# MPU.net
KiCad netlist of a schematic drawn in Altium Designer
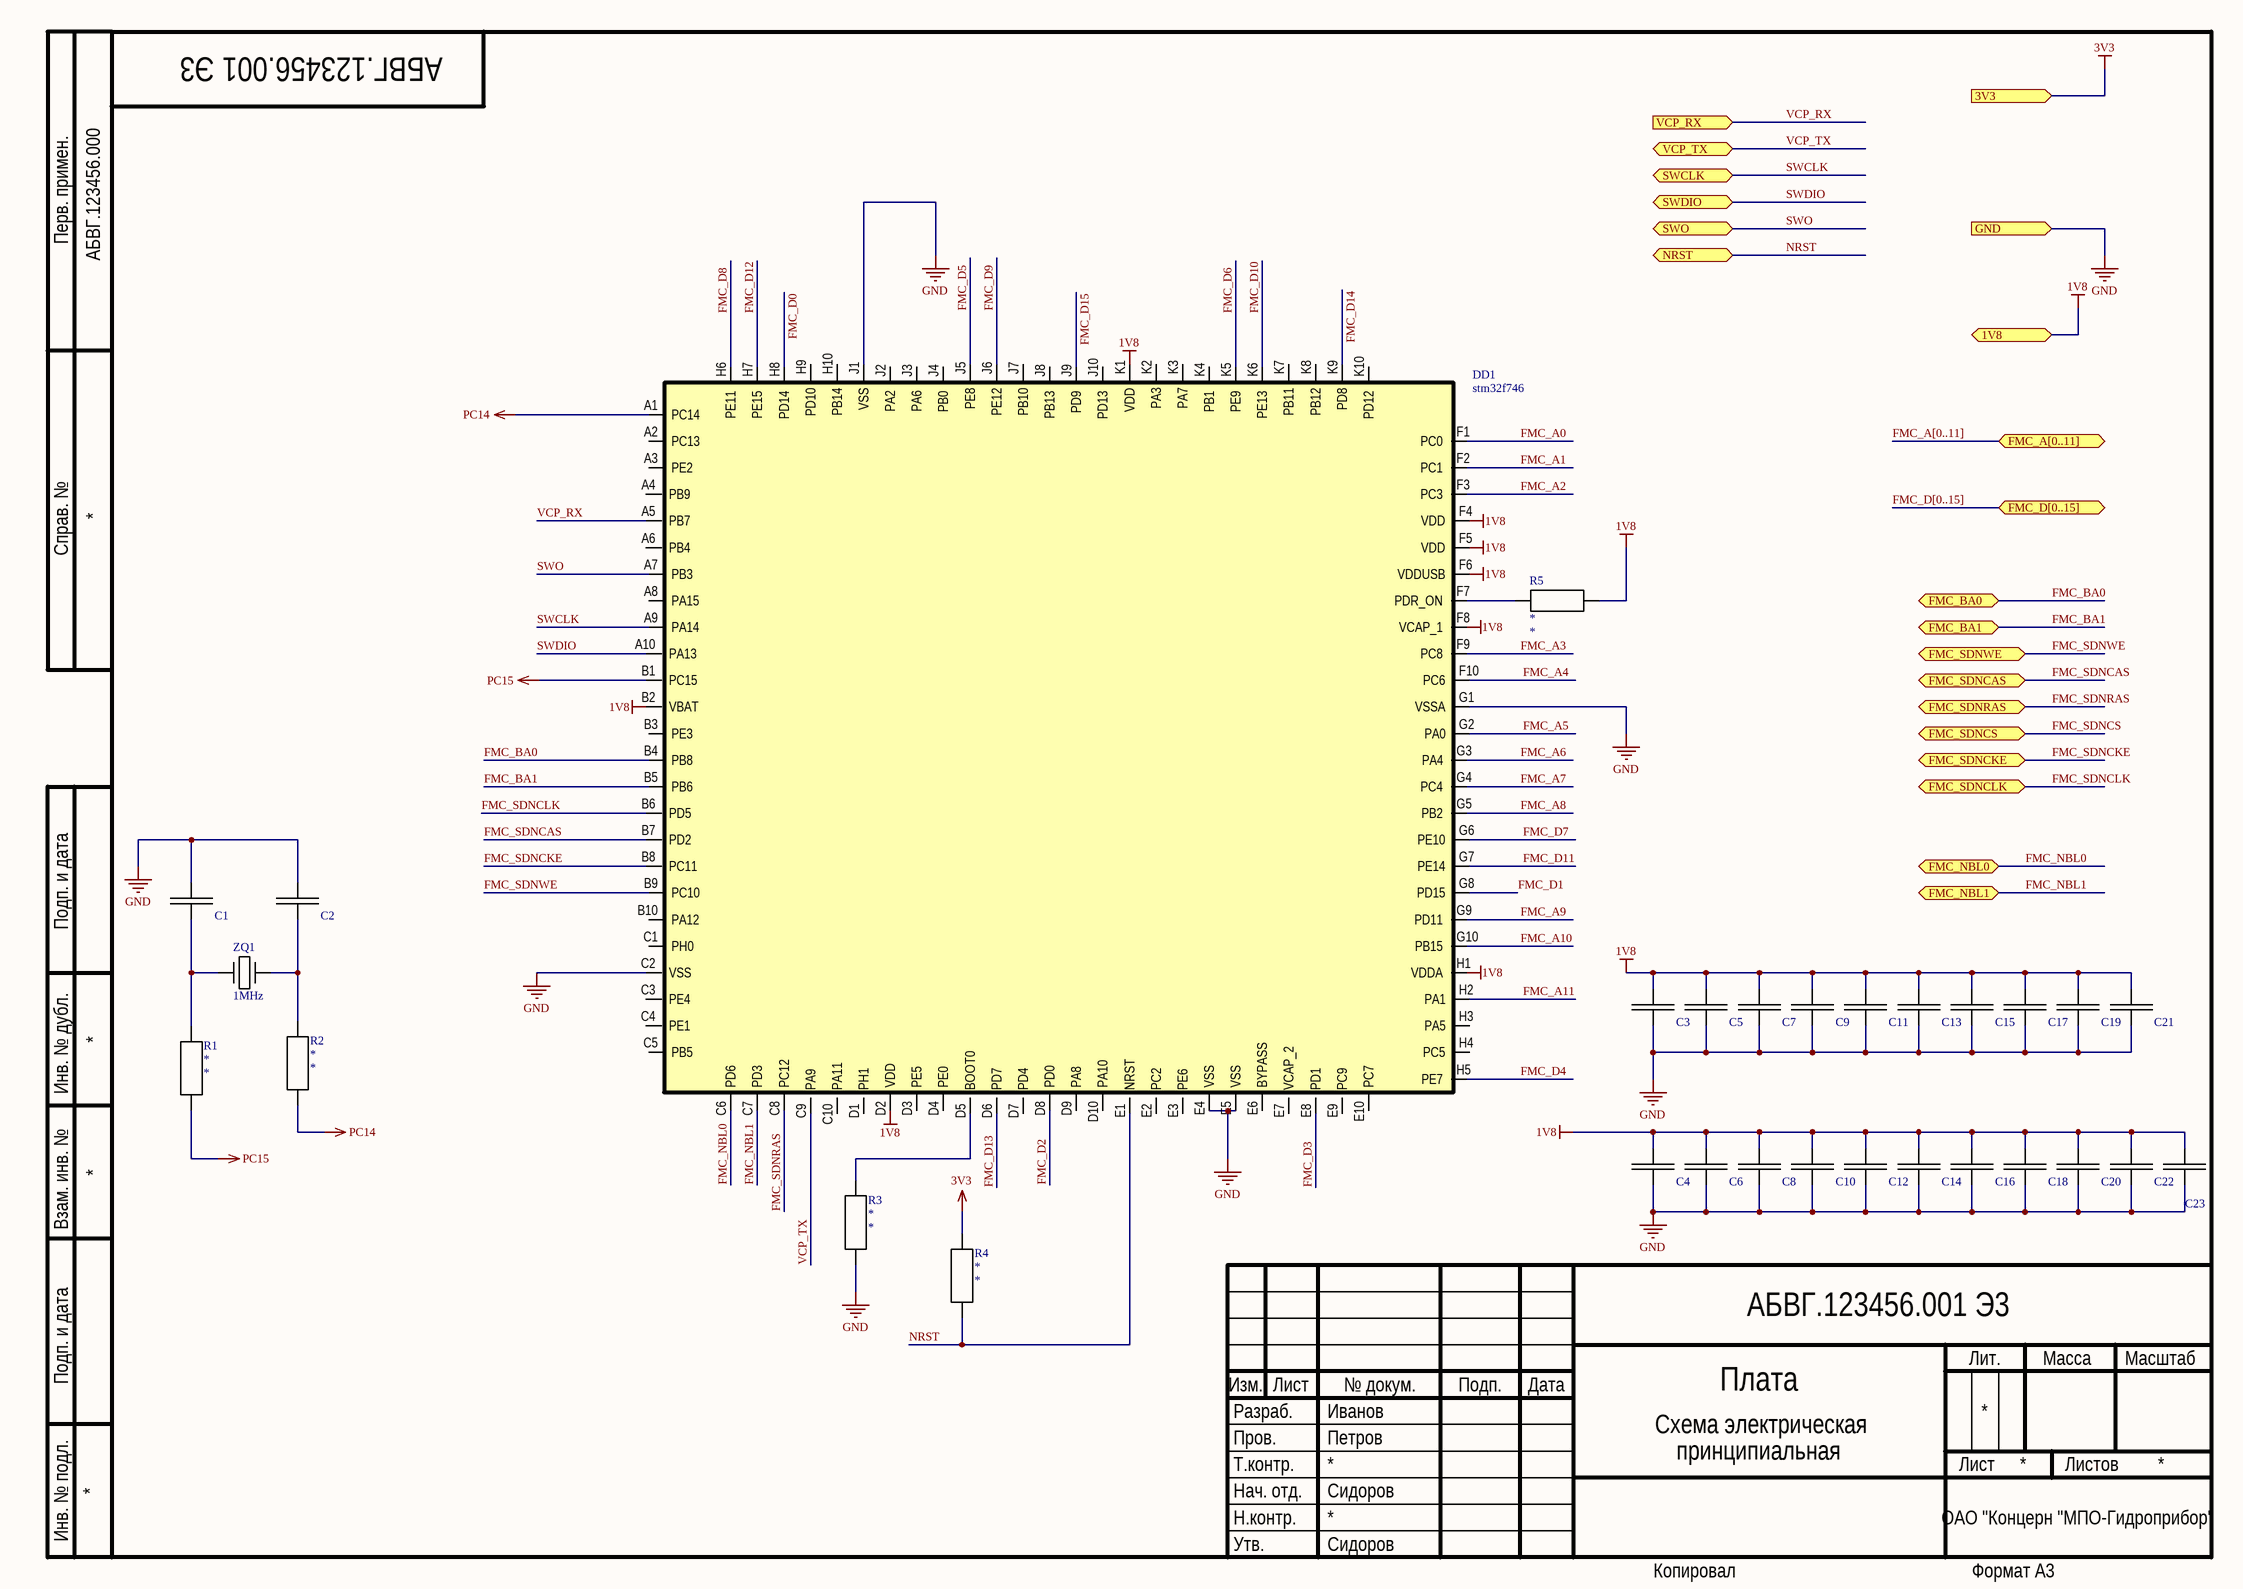
[diagram p0: MPU.SchDoc]

(export (version "E")
  (design (tool "Eeschema 10.0.6"))
  (components
    (comp (ref "C1") (value "*") (footprint "CAP0402") (libsource (lib "SchlibUGO") (part "Capasitor")))
    (comp (ref "C2") (value "*") (footprint "CAP0402") (libsource (lib "SchlibUGO") (part "Capasitor")))
    (comp (ref "C3") (value "*") (footprint "CAP0402") (libsource (lib "SchlibUGO") (part "Capasitor")))
    (comp (ref "C4") (value "*") (footprint "CAP0402") (libsource (lib "SchlibUGO") (part "Capasitor")))
    (comp (ref "C5") (value "*") (footprint "CAP0402") (libsource (lib "SchlibUGO") (part "Capasitor")))
    (comp (ref "C6") (value "*") (footprint "CAP0402") (libsource (lib "SchlibUGO") (part "Capasitor")))
    (comp (ref "C7") (value "*") (footprint "CAP0402") (libsource (lib "SchlibUGO") (part "Capasitor")))
    (comp (ref "C8") (value "*") (footprint "CAP0402") (libsource (lib "SchlibUGO") (part "Capasitor")))
    (comp (ref "C9") (value "*") (footprint "CAP0402") (libsource (lib "SchlibUGO") (part "Capasitor")))
    (comp (ref "C10") (value "*") (footprint "CAP0402") (libsource (lib "SchlibUGO") (part "Capasitor")))
    (comp (ref "C11") (value "*") (footprint "CAP0402") (libsource (lib "SchlibUGO") (part "Capasitor")))
    (comp (ref "C12") (value "*") (footprint "CAP0402") (libsource (lib "SchlibUGO") (part "Capasitor")))
    (comp (ref "C13") (value "*") (footprint "CAP0402") (libsource (lib "SchlibUGO") (part "Capasitor")))
    (comp (ref "C14") (value "*") (footprint "CAP0402") (libsource (lib "SchlibUGO") (part "Capasitor")))
    (comp (ref "C15") (value "*") (footprint "CAP0402") (libsource (lib "SchlibUGO") (part "Capasitor")))
    (comp (ref "C16") (value "*") (footprint "CAP0402") (libsource (lib "SchlibUGO") (part "Capasitor")))
    (comp (ref "C17") (value "*") (footprint "CAP0402") (libsource (lib "SchlibUGO") (part "Capasitor")))
    (comp (ref "C18") (value "*") (footprint "CAP0402") (libsource (lib "SchlibUGO") (part "Capasitor")))
    (comp (ref "C19") (value "*") (footprint "CAP0402") (libsource (lib "SchlibUGO") (part "Capasitor")))
    (comp (ref "C20") (value "*") (footprint "CAP0402") (libsource (lib "SchlibUGO") (part "Capasitor")))
    (comp (ref "C21") (value "*") (footprint "CAP0402") (libsource (lib "SchlibUGO") (part "Capasitor")))
    (comp (ref "C22") (value "*") (footprint "CAP0402") (libsource (lib "SchlibUGO") (part "Capasitor")))
    (comp (ref "C23") (value "*") (footprint "CAP0402") (libsource (lib "SchlibUGO") (part "Capasitor")))
    (comp (ref "DD1")
      (value "stm32f746")
      (footprint "BGA100P9X9-81A")
      (fields (field (name "MANUFACTURER") "STM"))
      (libsource (lib "SchlibUGO") (part "stm32f746"))
    )
    (comp (ref "R1")
      (value "*")
      (footprint "0402")
      (fields (field (name "ALTIUM_VALUE") "*") (field (name "POWER") "*"))
      (libsource (lib "SchlibUGO") (part "Resistor"))
    )
    (comp (ref "R2")
      (value "*")
      (footprint "0402")
      (fields (field (name "ALTIUM_VALUE") "*") (field (name "POWER") "*"))
      (libsource (lib "SchlibUGO") (part "Resistor"))
    )
    (comp (ref "R3")
      (value "*")
      (footprint "0402")
      (fields (field (name "ALTIUM_VALUE") "*") (field (name "POWER") "*"))
      (libsource (lib "SchlibUGO") (part "Resistor"))
    )
    (comp (ref "R4")
      (value "*")
      (footprint "0402")
      (fields (field (name "ALTIUM_VALUE") "*") (field (name "POWER") "*"))
      (libsource (lib "SchlibUGO") (part "Resistor"))
    )
    (comp (ref "R5")
      (value "*")
      (footprint "0402")
      (fields (field (name "ALTIUM_VALUE") "*") (field (name "POWER") "*"))
      (libsource (lib "SchlibUGO") (part "Resistor"))
    )
    (comp (ref "ZQ1")
      (value "1MHz")
      (footprint "KX-7")
      (fields (field (name "PART NUMBER") "HC-51") (field (name "MANUFACTURER") "CHina"))
      (libsource (lib "SchlibUGO") (part "Rzanator"))
    )
  )
  (nets
    (net (code "1") (name "/FMC_A0") (class "Default")
      (node (ref "DD1") (pin "F1") (pinfunction "PC0_F1") (pintype "passive"))
    )
    (net (code "2") (name "/FMC_A1") (class "Default")
      (node (ref "DD1") (pin "F2") (pinfunction "PC1_F2") (pintype "passive"))
    )
    (net (code "3") (name "/FMC_A2") (class "Default")
      (node (ref "DD1") (pin "F3") (pinfunction "PC3_F3") (pintype "passive"))
    )
    (net (code "4") (name "/FMC_A3") (class "Default")
      (node (ref "DD1") (pin "F9") (pinfunction "PC8_F9") (pintype "passive"))
    )
    (net (code "5") (name "/FMC_A4") (class "Default")
      (node (ref "DD1") (pin "F10") (pinfunction "PC6_F10") (pintype "passive"))
    )
    (net (code "6") (name "/FMC_A5") (class "Default")
      (node (ref "DD1") (pin "G2") (pinfunction "PA0_G2") (pintype "passive"))
    )
    (net (code "7") (name "/FMC_A6") (class "Default")
      (node (ref "DD1") (pin "G3") (pinfunction "PA4_G3") (pintype "passive"))
    )
    (net (code "8") (name "/FMC_A7") (class "Default")
      (node (ref "DD1") (pin "G4") (pinfunction "PC4_G4") (pintype "passive"))
    )
    (net (code "9") (name "/FMC_A8") (class "Default")
      (node (ref "DD1") (pin "G5") (pinfunction "PB2_G5") (pintype "passive"))
    )
    (net (code "10") (name "/FMC_A9") (class "Default")
      (node (ref "DD1") (pin "G9") (pinfunction "PD11_G9") (pintype "passive"))
    )
    (net (code "11") (name "/FMC_A10") (class "Default")
      (node (ref "DD1") (pin "G10") (pinfunction "PB15_G10") (pintype "passive"))
    )
    (net (code "12") (name "/FMC_A11") (class "Default")
      (node (ref "DD1") (pin "H2") (pinfunction "PA1_H2") (pintype "passive"))
    )
    (net (code "14") (name "/FMC_BA0") (class "Default")
      (node (ref "DD1") (pin "B4") (pinfunction "PB8_B4") (pintype "passive"))
    )
    (net (code "15") (name "/FMC_BA1") (class "Default")
      (node (ref "DD1") (pin "B5") (pinfunction "PB6_B5") (pintype "passive"))
    )
    (net (code "16") (name "/FMC_D0") (class "Default")
      (node (ref "DD1") (pin "H8") (pinfunction "PD14_H8") (pintype "passive"))
    )
    (net (code "17") (name "/FMC_D1") (class "Default")
      (node (ref "DD1") (pin "G8") (pinfunction "PD15_G8") (pintype "passive"))
    )
    (net (code "18") (name "/FMC_D2") (class "Default")
      (node (ref "DD1") (pin "D8") (pinfunction "PD0_D8") (pintype "passive"))
    )
    (net (code "19") (name "/FMC_D3") (class "Default")
      (node (ref "DD1") (pin "E8") (pinfunction "PD1_E8") (pintype "passive"))
    )
    (net (code "20") (name "/FMC_D4") (class "Default")
      (node (ref "DD1") (pin "H5") (pinfunction "PE7_H5") (pintype "passive"))
    )
    (net (code "21") (name "/FMC_D5") (class "Default")
      (node (ref "DD1") (pin "J5") (pinfunction "PE8_J5") (pintype "passive"))
    )
    (net (code "22") (name "/FMC_D6") (class "Default")
      (node (ref "DD1") (pin "K5") (pinfunction "PE9_K5") (pintype "passive"))
    )
    (net (code "23") (name "/FMC_D7") (class "Default")
      (node (ref "DD1") (pin "G6") (pinfunction "PE10_G6") (pintype "passive"))
    )
    (net (code "24") (name "/FMC_D8") (class "Default")
      (node (ref "DD1") (pin "H6") (pinfunction "PE11_H6") (pintype "passive"))
    )
    (net (code "25") (name "/FMC_D9") (class "Default")
      (node (ref "DD1") (pin "J6") (pinfunction "PE12_J6") (pintype "passive"))
    )
    (net (code "26") (name "/FMC_D10") (class "Default")
      (node (ref "DD1") (pin "K6") (pinfunction "PE13_K6") (pintype "passive"))
    )
    (net (code "27") (name "/FMC_D11") (class "Default")
      (node (ref "DD1") (pin "G7") (pinfunction "PE14_G7") (pintype "passive"))
    )
    (net (code "28") (name "/FMC_D12") (class "Default")
      (node (ref "DD1") (pin "H7") (pinfunction "PE15_H7") (pintype "passive"))
    )
    (net (code "29") (name "/FMC_D13") (class "Default")
      (node (ref "DD1") (pin "D6") (pinfunction "PD7_D6") (pintype "passive"))
    )
    (net (code "30") (name "/FMC_D14") (class "Default")
      (node (ref "DD1") (pin "K9") (pinfunction "PD8_K9") (pintype "passive"))
    )
    (net (code "31") (name "/FMC_D15") (class "Default")
      (node (ref "DD1") (pin "J9") (pinfunction "PD9_J9") (pintype "passive"))
    )
    (net (code "33") (name "/FMC_NBL0") (class "Default")
      (node (ref "DD1") (pin "C6") (pinfunction "PD6_C6") (pintype "passive"))
    )
    (net (code "34") (name "/FMC_NBL1") (class "Default")
      (node (ref "DD1") (pin "C7") (pinfunction "PD3_C7") (pintype "passive"))
    )
    (net (code "35") (name "/FMC_SDNCAS") (class "Default")
      (node (ref "DD1") (pin "B7") (pinfunction "PD2_B7") (pintype "passive"))
    )
    (net (code "36") (name "/FMC_SDNCKE") (class "Default")
      (node (ref "DD1") (pin "B8") (pinfunction "PC11_B8") (pintype "passive"))
    )
    (net (code "37") (name "/FMC_SDNCLK") (class "Default")
      (node (ref "DD1") (pin "B6") (pinfunction "PD5_B6") (pintype "passive"))
    )
    (net (code "39") (name "/FMC_SDNRAS") (class "Default")
      (node (ref "DD1") (pin "C8") (pinfunction "PC12_C8") (pintype "passive"))
    )
    (net (code "40") (name "/FMC_SDNWE") (class "Default")
      (node (ref "DD1") (pin "B9") (pinfunction "PC10_B9") (pintype "passive"))
    )
    (net (code "41") (name "/NRST") (class "Default")
      (node (ref "DD1") (pin "E1") (pinfunction "NRST_E1") (pintype "passive"))
      (node (ref "R4") (pin "1") (pinfunction "1_1") (pintype "passive"))
    )
    (net (code "42") (name "/SWCLK") (class "Default")
      (node (ref "DD1") (pin "A9") (pinfunction "PA14_A9") (pintype "passive"))
    )
    (net (code "43") (name "/SWDIO") (class "Default")
      (node (ref "DD1") (pin "A10") (pinfunction "PA13_A10") (pintype "passive"))
    )
    (net (code "44") (name "/SWO") (class "Default")
      (node (ref "DD1") (pin "A7") (pinfunction "PB3_A7") (pintype "passive"))
    )
    (net (code "45") (name "/VCP_RX") (class "Default")
      (node (ref "DD1") (pin "A5") (pinfunction "PB7_A5") (pintype "passive"))
    )
    (net (code "46") (name "/VCP_TX") (class "Default")
      (node (ref "DD1") (pin "C9") (pinfunction "PA9_C9") (pintype "passive"))
    )
    (net (code "47") (name "1V8") (class "Default")
      (node (ref "C10") (pin "1") (pinfunction "1_1") (pintype "passive"))
      (node (ref "C11") (pin "1") (pinfunction "1_1") (pintype "passive"))
      (node (ref "C12") (pin "1") (pinfunction "1_1") (pintype "passive"))
      (node (ref "C13") (pin "1") (pinfunction "1_1") (pintype "passive"))
      (node (ref "C14") (pin "1") (pinfunction "1_1") (pintype "passive"))
      (node (ref "C15") (pin "1") (pinfunction "1_1") (pintype "passive"))
      (node (ref "C16") (pin "1") (pinfunction "1_1") (pintype "passive"))
      (node (ref "C17") (pin "1") (pinfunction "1_1") (pintype "passive"))
      (node (ref "C18") (pin "1") (pinfunction "1_1") (pintype "passive"))
      (node (ref "C19") (pin "1") (pinfunction "1_1") (pintype "passive"))
      (node (ref "C20") (pin "1") (pinfunction "1_1") (pintype "passive"))
      (node (ref "C21") (pin "1") (pinfunction "1_1") (pintype "passive"))
      (node (ref "C22") (pin "1") (pinfunction "1_1") (pintype "passive"))
      (node (ref "C23") (pin "1") (pinfunction "1_1") (pintype "passive"))
      (node (ref "C3") (pin "1") (pinfunction "1_1") (pintype "passive"))
      (node (ref "C4") (pin "1") (pinfunction "1_1") (pintype "passive"))
      (node (ref "C5") (pin "1") (pinfunction "1_1") (pintype "passive"))
      (node (ref "C6") (pin "1") (pinfunction "1_1") (pintype "passive"))
      (node (ref "C7") (pin "1") (pinfunction "1_1") (pintype "passive"))
      (node (ref "C8") (pin "1") (pinfunction "1_1") (pintype "passive"))
      (node (ref "C9") (pin "1") (pinfunction "1_1") (pintype "passive"))
      (node (ref "DD1") (pin "B2") (pinfunction "VBAT_B2") (pintype "passive"))
      (node (ref "DD1") (pin "D2") (pinfunction "VDD_D2") (pintype "passive"))
      (node (ref "DD1") (pin "F4") (pinfunction "VDD_F4") (pintype "passive"))
      (node (ref "DD1") (pin "F5") (pinfunction "VDD_F5") (pintype "passive"))
      (node (ref "DD1") (pin "F6") (pinfunction "VDDUSB_F6") (pintype "passive"))
      (node (ref "DD1") (pin "F8") (pinfunction "VCAP_1_F8") (pintype "passive"))
      (node (ref "DD1") (pin "H1") (pinfunction "VDDA_H1") (pintype "passive"))
      (node (ref "DD1") (pin "K1") (pinfunction "VDD_K1") (pintype "passive"))
      (node (ref "R5") (pin "1") (pinfunction "1_1") (pintype "passive"))
    )
    (net (code "48") (name "3V3") (class "Default")
      (node (ref "R4") (pin "2") (pinfunction "2_2") (pintype "passive"))
    )
    (net (code "49") (name "GND") (class "Default")
      (node (ref "C1") (pin "1") (pinfunction "1_1") (pintype "passive"))
      (node (ref "C10") (pin "2") (pinfunction "2_2") (pintype "passive"))
      (node (ref "C11") (pin "2") (pinfunction "2_2") (pintype "passive"))
      (node (ref "C12") (pin "2") (pinfunction "2_2") (pintype "passive"))
      (node (ref "C13") (pin "2") (pinfunction "2_2") (pintype "passive"))
      (node (ref "C14") (pin "2") (pinfunction "2_2") (pintype "passive"))
      (node (ref "C15") (pin "2") (pinfunction "2_2") (pintype "passive"))
      (node (ref "C16") (pin "2") (pinfunction "2_2") (pintype "passive"))
      (node (ref "C17") (pin "2") (pinfunction "2_2") (pintype "passive"))
      (node (ref "C18") (pin "2") (pinfunction "2_2") (pintype "passive"))
      (node (ref "C19") (pin "2") (pinfunction "2_2") (pintype "passive"))
      (node (ref "C2") (pin "1") (pinfunction "1_1") (pintype "passive"))
      (node (ref "C20") (pin "2") (pinfunction "2_2") (pintype "passive"))
      (node (ref "C21") (pin "2") (pinfunction "2_2") (pintype "passive"))
      (node (ref "C22") (pin "2") (pinfunction "2_2") (pintype "passive"))
      (node (ref "C23") (pin "2") (pinfunction "2_2") (pintype "passive"))
      (node (ref "C3") (pin "2") (pinfunction "2_2") (pintype "passive"))
      (node (ref "C4") (pin "2") (pinfunction "2_2") (pintype "passive"))
      (node (ref "C5") (pin "2") (pinfunction "2_2") (pintype "passive"))
      (node (ref "C6") (pin "2") (pinfunction "2_2") (pintype "passive"))
      (node (ref "C7") (pin "2") (pinfunction "2_2") (pintype "passive"))
      (node (ref "C8") (pin "2") (pinfunction "2_2") (pintype "passive"))
      (node (ref "C9") (pin "2") (pinfunction "2_2") (pintype "passive"))
      (node (ref "DD1") (pin "C2") (pinfunction "VSS_C2") (pintype "passive"))
      (node (ref "DD1") (pin "E4") (pinfunction "VSS_E4") (pintype "passive"))
      (node (ref "DD1") (pin "E5") (pinfunction "VSS_E5") (pintype "passive"))
      (node (ref "DD1") (pin "G1") (pinfunction "VSSA_G1") (pintype "passive"))
      (node (ref "DD1") (pin "J1") (pinfunction "VSS_J1") (pintype "passive"))
      (node (ref "R3") (pin "1") (pinfunction "1_1") (pintype "passive"))
    )
    (net (code "50") (name "Net-(C1-Pad2)") (class "Default")
      (node (ref "C1") (pin "2") (pinfunction "2_2") (pintype "passive"))
      (node (ref "R1") (pin "2") (pinfunction "2_2") (pintype "passive"))
      (node (ref "ZQ1") (pin "1") (pinfunction "1_1") (pintype "passive"))
    )
    (net (code "51") (name "Net-(DD1-BOOT0)") (class "Default")
      (node (ref "DD1") (pin "D5") (pinfunction "BOOT0_D5") (pintype "passive"))
      (node (ref "R3") (pin "2") (pinfunction "2_2") (pintype "passive"))
    )
    (net (code "52") (name "Net-(DD1-PDR_ON)") (class "Default")
      (node (ref "DD1") (pin "F7") (pinfunction "PDR_ON_F7") (pintype "passive"))
      (node (ref "R5") (pin "2") (pinfunction "2_2") (pintype "passive"))
    )
    (net (code "53") (name "Net-(ZQ1-2)") (class "Default")
      (node (ref "C2") (pin "2") (pinfunction "2_2") (pintype "passive"))
      (node (ref "R2") (pin "2") (pinfunction "2_2") (pintype "passive"))
      (node (ref "ZQ1") (pin "3") (pinfunction "2_3") (pintype "passive"))
    )
    (net (code "54") (name "PC14") (class "Default")
      (node (ref "DD1") (pin "A1") (pinfunction "PC14_A1") (pintype "passive"))
      (node (ref "R2") (pin "1") (pinfunction "1_1") (pintype "passive"))
    )
    (net (code "55") (name "PC15") (class "Default")
      (node (ref "DD1") (pin "B1") (pinfunction "PC15_B1") (pintype "passive"))
      (node (ref "R1") (pin "1") (pinfunction "1_1") (pintype "passive"))
    )
    (net (code "56") (name "unconnected-(DD1-BYPASS-PadE6)") (class "Default")
      (node (ref "DD1") (pin "E6") (pinfunction "BYPASS_E6") (pintype "passive"))
    )
    (net (code "57") (name "unconnected-(DD1-PA2-PadJ2)") (class "Default")
      (node (ref "DD1") (pin "J2") (pinfunction "PA2_J2") (pintype "passive"))
    )
    (net (code "58") (name "unconnected-(DD1-PA3-PadK2)") (class "Default")
      (node (ref "DD1") (pin "K2") (pinfunction "PA3_K2") (pintype "passive"))
    )
    (net (code "59") (name "unconnected-(DD1-PA5-PadH3)") (class "Default")
      (node (ref "DD1") (pin "H3") (pinfunction "PA5_H3") (pintype "passive"))
    )
    (net (code "60") (name "unconnected-(DD1-PA6-PadJ3)") (class "Default")
      (node (ref "DD1") (pin "J3") (pinfunction "PA6_J3") (pintype "passive"))
    )
    (net (code "61") (name "unconnected-(DD1-PA7-PadK3)") (class "Default")
      (node (ref "DD1") (pin "K3") (pinfunction "PA7_K3") (pintype "passive"))
    )
    (net (code "62") (name "unconnected-(DD1-PA8-PadD9)") (class "Default")
      (node (ref "DD1") (pin "D9") (pinfunction "PA8_D9") (pintype "passive"))
    )
    (net (code "63") (name "unconnected-(DD1-PA10-PadD10)") (class "Default")
      (node (ref "DD1") (pin "D10") (pinfunction "PA10_D10") (pintype "passive"))
    )
    (net (code "64") (name "unconnected-(DD1-PA11-PadC10)") (class "Default")
      (node (ref "DD1") (pin "C10") (pinfunction "PA11_C10") (pintype "passive"))
    )
    (net (code "65") (name "unconnected-(DD1-PA12-PadB10)") (class "Default")
      (node (ref "DD1") (pin "B10") (pinfunction "PA12_B10") (pintype "passive"))
    )
    (net (code "66") (name "unconnected-(DD1-PA15-PadA8)") (class "Default")
      (node (ref "DD1") (pin "A8") (pinfunction "PA15_A8") (pintype "passive"))
    )
    (net (code "67") (name "unconnected-(DD1-PB0-PadJ4)") (class "Default")
      (node (ref "DD1") (pin "J4") (pinfunction "PB0_J4") (pintype "passive"))
    )
    (net (code "68") (name "unconnected-(DD1-PB1-PadK4)") (class "Default")
      (node (ref "DD1") (pin "K4") (pinfunction "PB1_K4") (pintype "passive"))
    )
    (net (code "69") (name "unconnected-(DD1-PB4-PadA6)") (class "Default")
      (node (ref "DD1") (pin "A6") (pinfunction "PB4_A6") (pintype "passive"))
    )
    (net (code "70") (name "unconnected-(DD1-PB5-PadC5)") (class "Default")
      (node (ref "DD1") (pin "C5") (pinfunction "PB5_C5") (pintype "passive"))
    )
    (net (code "71") (name "unconnected-(DD1-PB9-PadA4)") (class "Default")
      (node (ref "DD1") (pin "A4") (pinfunction "PB9_A4") (pintype "passive"))
    )
    (net (code "72") (name "unconnected-(DD1-PB10-PadJ7)") (class "Default")
      (node (ref "DD1") (pin "J7") (pinfunction "PB10_J7") (pintype "passive"))
    )
    (net (code "73") (name "unconnected-(DD1-PB11-PadK7)") (class "Default")
      (node (ref "DD1") (pin "K7") (pinfunction "PB11_K7") (pintype "passive"))
    )
    (net (code "74") (name "unconnected-(DD1-PB12-PadK8)") (class "Default")
      (node (ref "DD1") (pin "K8") (pinfunction "PB12_K8") (pintype "passive"))
    )
    (net (code "75") (name "unconnected-(DD1-PB13-PadJ8)") (class "Default")
      (node (ref "DD1") (pin "J8") (pinfunction "PB13_J8") (pintype "passive"))
    )
    (net (code "76") (name "unconnected-(DD1-PB14-PadH10)") (class "Default")
      (node (ref "DD1") (pin "H10") (pinfunction "PB14_H10") (pintype "passive"))
    )
    (net (code "77") (name "unconnected-(DD1-PC2-PadE2)") (class "Default")
      (node (ref "DD1") (pin "E2") (pinfunction "PC2_E2") (pintype "passive"))
    )
    (net (code "78") (name "unconnected-(DD1-PC5-PadH4)") (class "Default")
      (node (ref "DD1") (pin "H4") (pinfunction "PC5_H4") (pintype "passive"))
    )
    (net (code "79") (name "unconnected-(DD1-PC7-PadE10)") (class "Default")
      (node (ref "DD1") (pin "E10") (pinfunction "PC7_E10") (pintype "passive"))
    )
    (net (code "80") (name "unconnected-(DD1-PC9-PadE9)") (class "Default")
      (node (ref "DD1") (pin "E9") (pinfunction "PC9_E9") (pintype "passive"))
    )
    (net (code "81") (name "unconnected-(DD1-PC13-PadA2)") (class "Default")
      (node (ref "DD1") (pin "A2") (pinfunction "PC13_A2") (pintype "passive"))
    )
    (net (code "82") (name "unconnected-(DD1-PD4-PadD7)") (class "Default")
      (node (ref "DD1") (pin "D7") (pinfunction "PD4_D7") (pintype "passive"))
    )
    (net (code "83") (name "unconnected-(DD1-PD10-PadH9)") (class "Default")
      (node (ref "DD1") (pin "H9") (pinfunction "PD10_H9") (pintype "passive"))
    )
    (net (code "84") (name "unconnected-(DD1-PD12-PadK10)") (class "Default")
      (node (ref "DD1") (pin "K10") (pinfunction "PD12_K10") (pintype "passive"))
    )
    (net (code "85") (name "unconnected-(DD1-PD13-PadJ10)") (class "Default")
      (node (ref "DD1") (pin "J10") (pinfunction "PD13_J10") (pintype "passive"))
    )
    (net (code "86") (name "unconnected-(DD1-PE0-PadD4)") (class "Default")
      (node (ref "DD1") (pin "D4") (pinfunction "PE0_D4") (pintype "passive"))
    )
    (net (code "87") (name "unconnected-(DD1-PE1-PadC4)") (class "Default")
      (node (ref "DD1") (pin "C4") (pinfunction "PE1_C4") (pintype "passive"))
    )
    (net (code "88") (name "unconnected-(DD1-PE2-PadA3)") (class "Default")
      (node (ref "DD1") (pin "A3") (pinfunction "PE2_A3") (pintype "passive"))
    )
    (net (code "89") (name "unconnected-(DD1-PE3-PadB3)") (class "Default")
      (node (ref "DD1") (pin "B3") (pinfunction "PE3_B3") (pintype "passive"))
    )
    (net (code "90") (name "unconnected-(DD1-PE4-PadC3)") (class "Default")
      (node (ref "DD1") (pin "C3") (pinfunction "PE4_C3") (pintype "passive"))
    )
    (net (code "91") (name "unconnected-(DD1-PE5-PadD3)") (class "Default")
      (node (ref "DD1") (pin "D3") (pinfunction "PE5_D3") (pintype "passive"))
    )
    (net (code "92") (name "unconnected-(DD1-PE6-PadE3)") (class "Default")
      (node (ref "DD1") (pin "E3") (pinfunction "PE6_E3") (pintype "passive"))
    )
    (net (code "93") (name "unconnected-(DD1-PH0-PadC1)") (class "Default")
      (node (ref "DD1") (pin "C1") (pinfunction "PH0_C1") (pintype "passive"))
    )
    (net (code "94") (name "unconnected-(DD1-PH1-PadD1)") (class "Default")
      (node (ref "DD1") (pin "D1") (pinfunction "PH1_D1") (pintype "passive"))
    )
    (net (code "95") (name "unconnected-(DD1-VCAP_2-PadE7)") (class "Default")
      (node (ref "DD1") (pin "E7") (pinfunction "VCAP_2_E7") (pintype "passive"))
    )
  )
)
